# SCH_12V_5A_PSU_2023-10-23.net
KiCad netlist of a schematic drawn in EasyEDA
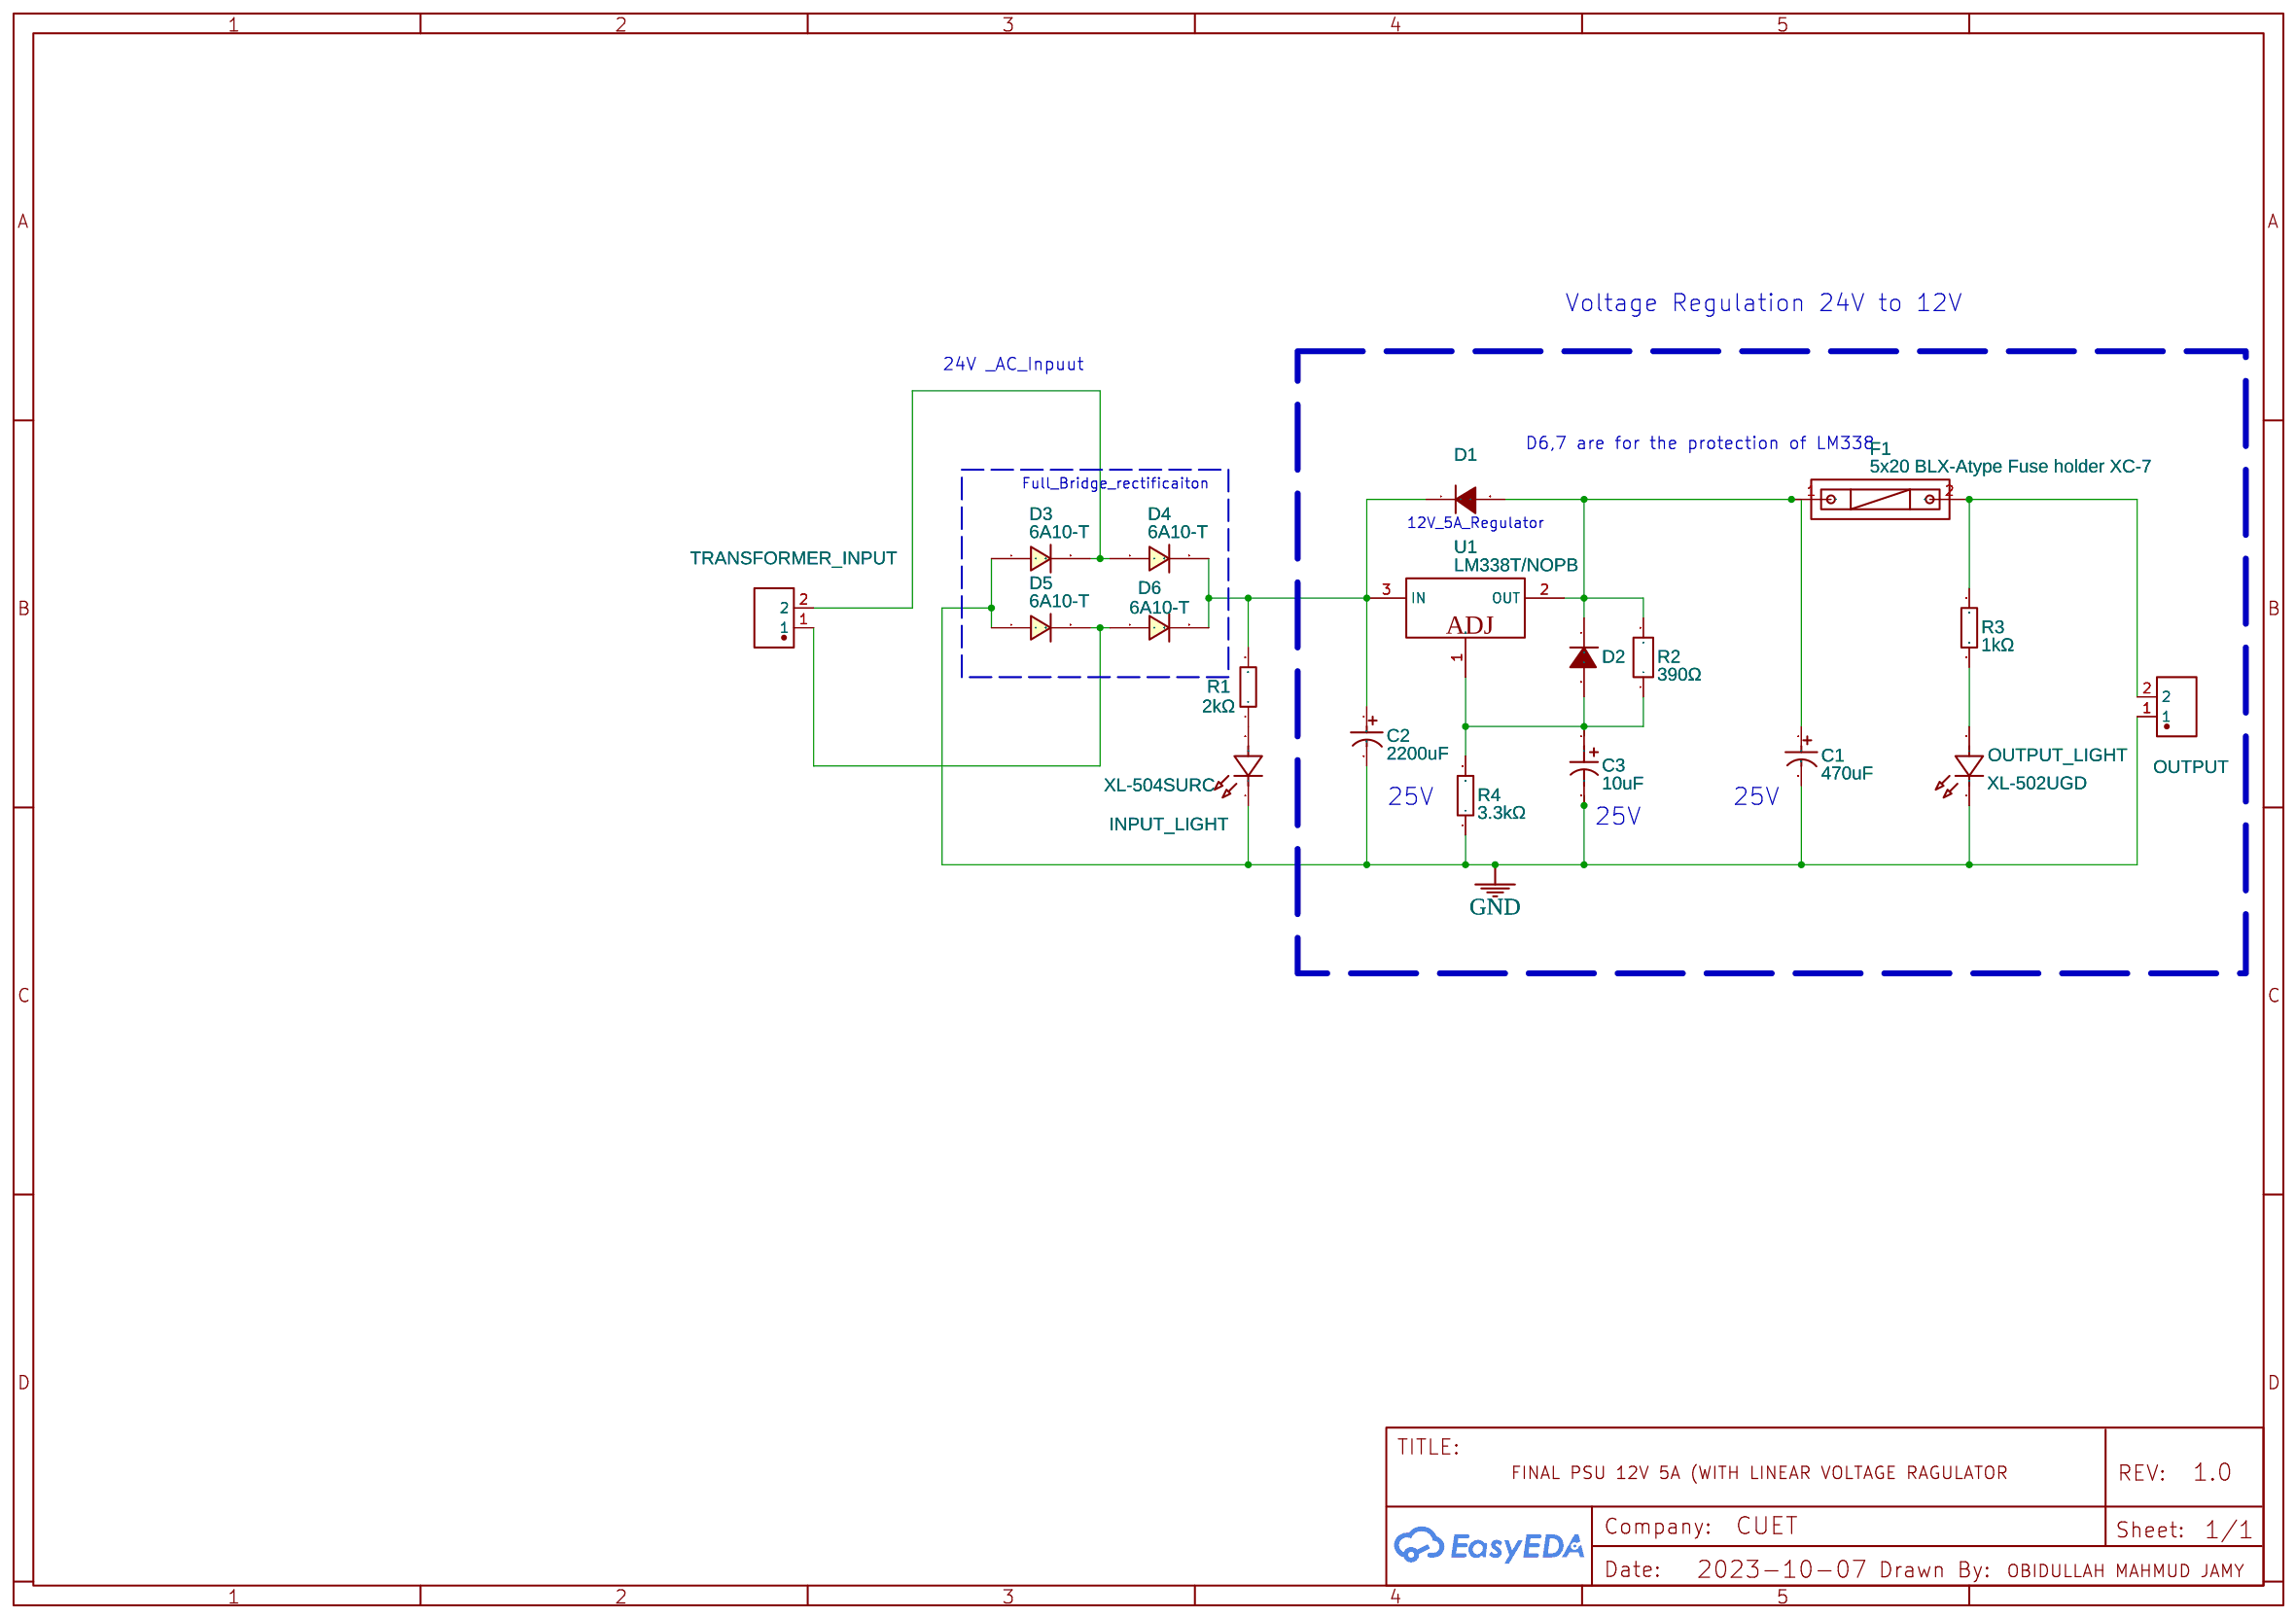
[diagram p0: schematic sheet]

(export (version "E")
  (design (tool "Eeschema 10.0.6"))
  (components
    (comp (ref "C1")
      (value "470uF")
      (fields
        (field (name "Manufacturer Part") "GR477M025F12RR0VH4FP0")
        (field (name "Manufacturer") "CX(承兴)")
      )
      (libsource (lib "") (part "470uF 25V 8*12Black high frequency"))
    )
    (comp (ref "C2")
      (value "2200uF")
      (fields
        (field (name "Manufacturer Part") "GR228M025J25RR0VZ2FP0")
        (field (name "Manufacturer") "CX(承兴)")
      )
      (libsource (lib "") (part "2200uF 25V 13*25VPurple high frequency"))
    )
    (comp (ref "C3")
      (value "10uF")
      (fields
        (field (name "Manufacturer Part") "EG22GM100F13CTBVZC-L=3.5")
        (field (name "Manufacturer") "Yunxing(云星)")
      )
      (libsource (lib "") (part "EG22GM100F13CTBVZC-L=3.5"))
    )
    (comp (ref "D1")
      (value "1N4007")
      (fields (field (name "Manufacturer") "ST(先科)"))
      (libsource (lib "") (part "1N4007_1"))
    )
    (comp (ref "D2")
      (value "1N4007")
      (fields (field (name "Manufacturer") "ST(先科)"))
      (libsource (lib "") (part "1N4007"))
    )
    (comp (ref "D3")
      (value "6A10-T")
      (fields (field (name "Manufacturer") "DIODES(美台)"))
      (libsource (lib "") (part "6A10-T"))
    )
    (comp (ref "D4")
      (value "6A10-T")
      (fields (field (name "Manufacturer") "DIODES(美台)"))
      (libsource (lib "") (part "6A10-T"))
    )
    (comp (ref "D5")
      (value "6A10-T")
      (fields (field (name "Manufacturer") "DIODES(美台)"))
      (libsource (lib "") (part "6A10-T"))
    )
    (comp (ref "D6")
      (value "6A10-T")
      (fields (field (name "Manufacturer") "DIODES(美台)"))
      (libsource (lib "") (part "6A10-T"))
    )
    (comp (ref "F1")
      (value "5x20 BLX-Atype Fuse holder XC-7")
      (fields
        (field (name "Manufacturer Part") "5x20 BLX-A型 保险丝支架 XC-7")
        (field (name "Manufacturer") "xcfuse(旭程)")
      )
      (libsource (lib "") (part "5x20 BLX-Atype Fuse holder XC-7"))
    )
    (comp (ref "INPUT_LIGHT")
      (value "XL-504SURC")
      (fields (field (name "Manufacturer") "XINGLIGHT(成兴光)"))
      (libsource (lib "") (part "XL-504SURC"))
    )
    (comp (ref "OUTPUT")
      (value "KF129-7.5-2P")
      (fields (field (name "Manufacturer") "KEFA(科发)"))
      (libsource (lib "") (part "KF129-7.5-2P_1"))
    )
    (comp (ref "OUTPUT_LIGHT")
      (value "XL-502UGD")
      (fields (field (name "Manufacturer") "XINGLIGHT(成兴光)"))
      (libsource (lib "") (part "XL-502UGD"))
    )
    (comp (ref "R1")
      (value "2kΩ")
      (fields (field (name "Manufacturer Part") "CF1/4W-2KΩ±5% T") (field (name "Manufacturer") "CCO(千志电子)"))
      (libsource (lib "") (part "CF1/4W-2KΩ±5% T52"))
    )
    (comp (ref "R2")
      (value "390Ω")
      (fields (field (name "Manufacturer Part") "CR1/4W-390Ω±5%-ST26") (field (name "Manufacturer") "VO(翔胜)"))
      (libsource (lib "") (part "CR1/4W-390Ω±5%-ST26"))
    )
    (comp (ref "R3")
      (value "1kΩ")
      (fields (field (name "Manufacturer Part") "MFR3WSJT-73-1K") (field (name "Manufacturer") "YAGEO(国巨)"))
      (libsource (lib "") (part "MFR3WSJT-73-1K"))
    )
    (comp (ref "R4")
      (value "3.3kΩ")
      (fields (field (name "Manufacturer Part") "CF1/4W-3.3KΩ±5%T52") (field (name "Manufacturer") "华星机电"))
      (libsource (lib "") (part "CF1/4W-3.3KΩ±5%T52"))
    )
    (comp (ref "TRANSFORMER_INPUT")
      (value "KF129-7.5-2P")
      (fields (field (name "Manufacturer") "KEFA(科发)"))
      (libsource (lib "") (part "KF129-7.5-2P"))
    )
    (comp (ref "U1")
      (value "LM338T/NOPB")
      (fields (field (name "Manufacturer") "TI(德州仪器)"))
      (libsource (lib "") (part "LM338T/NOPB"))
    )
  )
  (nets
    (net (code "1") (name "GND") (class "Default")
      (node (ref "C1") (pin "2") (pinfunction "2_2") (pintype "input"))
      (node (ref "C2") (pin "2") (pinfunction "2_2") (pintype "input"))
      (node (ref "C3") (pin "2") (pinfunction "2_2") (pintype "input"))
      (node (ref "D3") (pin "1") (pinfunction "A_1") (pintype "input"))
      (node (ref "D5") (pin "1") (pinfunction "A_1") (pintype "input"))
      (node (ref "INPUT_LIGHT") (pin "1") (pinfunction "K_1") (pintype "unspecified"))
      (node (ref "OUTPUT") (pin "1") (pinfunction "1_1") (pintype "unspecified"))
      (node (ref "OUTPUT_LIGHT") (pin "1") (pinfunction "K_1") (pintype "unspecified"))
      (node (ref "R4") (pin "1") (pinfunction "1_1") (pintype "unspecified"))
    )
    (net (code "2") (name "Net-(D1-A)") (class "Default")
      (node (ref "C1") (pin "1") (pinfunction "1_1") (pintype "input"))
      (node (ref "D1") (pin "2") (pinfunction "A_2") (pintype "unspecified"))
      (node (ref "D2") (pin "1") (pinfunction "K_1") (pintype "unspecified"))
      (node (ref "F1") (pin "1") (pinfunction "1_1") (pintype "unspecified"))
      (node (ref "R2") (pin "2") (pinfunction "2_2") (pintype "unspecified"))
      (node (ref "U1") (pin "2") (pinfunction "OUT_2") (pintype "passive"))
    )
    (net (code "3") (name "Net-(D1-K)") (class "Default")
      (node (ref "C2") (pin "1") (pinfunction "1_1") (pintype "input"))
      (node (ref "D1") (pin "1") (pinfunction "K_1") (pintype "unspecified"))
      (node (ref "D4") (pin "2") (pinfunction "C_2") (pintype "input"))
      (node (ref "D6") (pin "2") (pinfunction "C_2") (pintype "input"))
      (node (ref "R1") (pin "2") (pinfunction "2_2") (pintype "unspecified"))
      (node (ref "U1") (pin "3") (pinfunction "IN_3") (pintype "passive"))
    )
    (net (code "4") (name "Net-(D2-A)") (class "Default")
      (node (ref "C3") (pin "1") (pinfunction "1_1") (pintype "input"))
      (node (ref "D2") (pin "2") (pinfunction "A_2") (pintype "unspecified"))
      (node (ref "R2") (pin "1") (pinfunction "1_1") (pintype "unspecified"))
      (node (ref "R4") (pin "2") (pinfunction "2_2") (pintype "unspecified"))
      (node (ref "U1") (pin "1") (pinfunction "ADJ_1") (pintype "unspecified"))
    )
    (net (code "5") (name "Net-(D3-C)") (class "Default")
      (node (ref "D3") (pin "2") (pinfunction "C_2") (pintype "input"))
      (node (ref "D4") (pin "1") (pinfunction "A_1") (pintype "input"))
      (node (ref "TRANSFORMER_INPUT") (pin "2") (pinfunction "2_2") (pintype "unspecified"))
    )
    (net (code "6") (name "Net-(D5-C)") (class "Default")
      (node (ref "D5") (pin "2") (pinfunction "C_2") (pintype "input"))
      (node (ref "D6") (pin "1") (pinfunction "A_1") (pintype "input"))
      (node (ref "TRANSFORMER_INPUT") (pin "1") (pinfunction "1_1") (pintype "unspecified"))
    )
    (net (code "7") (name "Net-(F1-Pad2)") (class "Default")
      (node (ref "F1") (pin "2") (pinfunction "2_2") (pintype "unspecified"))
      (node (ref "OUTPUT") (pin "2") (pinfunction "2_2") (pintype "unspecified"))
      (node (ref "R3") (pin "2") (pinfunction "2_2") (pintype "unspecified"))
    )
    (net (code "8") (name "Net-(INPUT_LIGHT-A)") (class "Default")
      (node (ref "INPUT_LIGHT") (pin "2") (pinfunction "A_2") (pintype "unspecified"))
      (node (ref "R1") (pin "1") (pinfunction "1_1") (pintype "unspecified"))
    )
    (net (code "9") (name "Net-(OUTPUT_LIGHT-A)") (class "Default")
      (node (ref "OUTPUT_LIGHT") (pin "2") (pinfunction "A_2") (pintype "unspecified"))
      (node (ref "R3") (pin "1") (pinfunction "1_1") (pintype "unspecified"))
    )
  )
)
